# Versterkers.net
KiCad netlist of a schematic drawn in Altium Designer
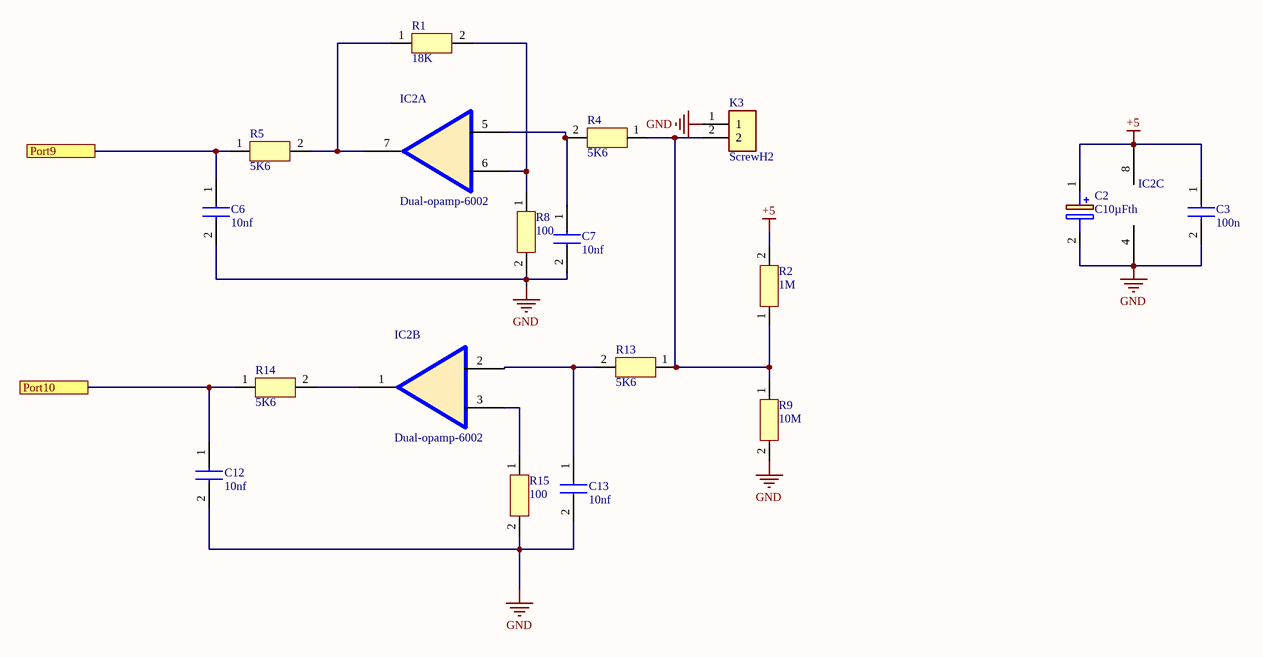
[diagram p0: Versterkers.SchDoc]

(export (version "E")
  (design (tool "Eeschema 10.0.6"))
  (components
    (comp (ref "C2")
      (value "C10µFth")
      (footprint "C10µFth")
      (description "Capacitor Polarised")
      (fields
        (field (name "MOUSER2 PART NUMBER") "667-ECA-1HM100I")
        (field (name "MANUFACTURER_PART_NUMBER") "ECA-1HM100I")
      )
      (libsource (lib "Soldeerbout_12002498") (part "C10µFth"))
    )
    (comp (ref "C3")
      (value "100n")
      (footprint "0805")
      (description "Capacitor")
      (fields (field (name "MANUFACTURER_PART_NUMBER") "C0805C301G5GACTU"))
      (libsource (lib "Soldeerbout_12002498") (part "C0805smd"))
    )
    (comp (ref "C6")
      (value "10nf")
      (footprint "0805")
      (description "Capacitor")
      (fields (field (name "MANUFACTURER_PART_NUMBER") "C0805C301G5GACTU"))
      (libsource (lib "Soldeerbout_12002498") (part "C0805smd"))
    )
    (comp (ref "C7")
      (value "10nf")
      (footprint "0805")
      (description "Capacitor")
      (fields (field (name "MANUFACTURER_PART_NUMBER") "C0805C301G5GACTU"))
      (libsource (lib "Soldeerbout_12002498") (part "C0805smd"))
    )
    (comp (ref "C12")
      (value "10nf")
      (footprint "0805")
      (description "Capacitor")
      (fields (field (name "MANUFACTURER_PART_NUMBER") "C0805C301G5GACTU"))
      (libsource (lib "Soldeerbout_12002498") (part "C0805smd"))
    )
    (comp (ref "C13")
      (value "10nf")
      (footprint "0805")
      (description "Capacitor")
      (fields (field (name "MANUFACTURER_PART_NUMBER") "C0805C301G5GACTU"))
      (libsource (lib "Soldeerbout_12002498") (part "C0805smd"))
    )
    (comp (ref "IC2")
      (value "Dual-opamp-6002")
      (footprint "Dual-opamp-6002")
      (description "Integrated Circuit")
      (fields
        (field (name "MOUSER2 PART NUMBER") "579-MCP6002-E/P")
        (field (name "MANUFACTURER_PART_NUMBER") "MCP6002-E/P")
      )
      (libsource (lib "Soldeerbout_12002498") (part "Dual-opamp-6002"))
    )
    (comp (ref "K3")
      (value "ScrewH2")
      (footprint "Soldeerbout_12002498:ScewH2")
      (description "Connector")
      (fields
        (field (name "MOUSER2 PART NUMBER") "490-TB007-508-02BE")
        (field (name "MANUFACTURER_PART_NUMBER") "TB007-508-02BE")
      )
      (libsource (lib "Soldeerbout_12002498") (part "ScrewH2"))
    )
    (comp (ref "R1")
      (value "18K")
      (footprint "0805")
      (description "Resistor")
      (fields (field (name "MANUFACTURER_PART_NUMBER") "TNPU0805500RAZEN00"))
      (libsource (lib "Soldeerbout_12002498") (part "R-0805"))
    )
    (comp (ref "R2")
      (value "1M")
      (footprint "0805")
      (description "Resistor")
      (fields (field (name "MANUFACTURER_PART_NUMBER") "TNPU0805500RAZEN00"))
      (libsource (lib "") (part "R-0805_2"))
    )
    (comp (ref "R4")
      (value "5K6")
      (footprint "0805")
      (description "Resistor")
      (fields (field (name "MANUFACTURER_PART_NUMBER") "TNPU0805500RAZEN00"))
      (libsource (lib "") (part "R-0805_3"))
    )
    (comp (ref "R5")
      (value "5K6")
      (footprint "0805")
      (description "Resistor")
      (fields (field (name "MANUFACTURER_PART_NUMBER") "TNPU0805500RAZEN00"))
      (libsource (lib "Soldeerbout_12002498") (part "R-0805"))
    )
    (comp (ref "R8")
      (value "100")
      (footprint "0805")
      (description "Resistor")
      (fields (field (name "MANUFACTURER_PART_NUMBER") "TNPU0805500RAZEN00"))
      (libsource (lib "") (part "R-0805_1"))
    )
    (comp (ref "R9")
      (value "10M")
      (footprint "0805")
      (description "Resistor")
      (fields (field (name "MANUFACTURER_PART_NUMBER") "TNPU0805500RAZEN00"))
      (libsource (lib "") (part "R-0805_1"))
    )
    (comp (ref "R13")
      (value "5K6")
      (footprint "0805")
      (description "Resistor")
      (fields (field (name "MANUFACTURER_PART_NUMBER") "TNPU0805500RAZEN00"))
      (libsource (lib "") (part "R-0805_3"))
    )
    (comp (ref "R14")
      (value "5K6")
      (footprint "0805")
      (description "Resistor")
      (fields (field (name "MANUFACTURER_PART_NUMBER") "TNPU0805500RAZEN00"))
      (libsource (lib "Soldeerbout_12002498") (part "R-0805"))
    )
    (comp (ref "R15")
      (value "100")
      (footprint "0805")
      (description "Resistor")
      (fields (field (name "MANUFACTURER_PART_NUMBER") "TNPU0805500RAZEN00"))
      (libsource (lib "") (part "R-0805_1"))
    )
  )
  (nets
    (net (code "1") (name "+5") (class "Default")
      (node (ref "C2") (pin "1") (pinfunction "+_1") (pintype "passive"))
      (node (ref "C3") (pin "1") (pinfunction "1_1") (pintype "passive"))
      (node (ref "IC2") (pin "8") (pinfunction "8_8") (pintype "passive"))
      (node (ref "R2") (pin "2") (pinfunction "2_2") (pintype "passive"))
    )
    (net (code "2") (name "/Port9") (class "Default")
      (node (ref "C6") (pin "1") (pinfunction "1_1") (pintype "passive"))
      (node (ref "R5") (pin "1") (pinfunction "1_1") (pintype "passive"))
    )
    (net (code "3") (name "/Port10") (class "Default")
      (node (ref "C12") (pin "1") (pinfunction "1_1") (pintype "passive"))
      (node (ref "R14") (pin "1") (pinfunction "1_1") (pintype "passive"))
    )
    (net (code "4") (name "GND") (class "Default")
      (node (ref "C12") (pin "2") (pinfunction "2_2") (pintype "passive"))
      (node (ref "C13") (pin "2") (pinfunction "2_2") (pintype "passive"))
      (node (ref "C2") (pin "2") (pinfunction "-_2") (pintype "passive"))
      (node (ref "C3") (pin "2") (pinfunction "2_2") (pintype "passive"))
      (node (ref "C6") (pin "2") (pinfunction "2_2") (pintype "passive"))
      (node (ref "C7") (pin "2") (pinfunction "2_2") (pintype "passive"))
      (node (ref "IC2") (pin "4") (pinfunction "9_4") (pintype "passive"))
      (node (ref "K3") (pin "1") (pinfunction "1_1") (pintype "passive"))
      (node (ref "R15") (pin "2") (pinfunction "2_2") (pintype "passive"))
      (node (ref "R8") (pin "2") (pinfunction "2_2") (pintype "passive"))
      (node (ref "R9") (pin "2") (pinfunction "2_2") (pintype "passive"))
    )
    (net (code "5") (name "Net-(IC2A-Vin)") (class "Default")
      (node (ref "C7") (pin "1") (pinfunction "1_1") (pintype "passive"))
      (node (ref "IC2") (pin "5") (pinfunction "Vin_5") (pintype "passive"))
      (node (ref "R4") (pin "2") (pinfunction "2_2") (pintype "passive"))
    )
    (net (code "6") (name "Net-(IC2A-Vin-)") (class "Default")
      (node (ref "IC2") (pin "6") (pinfunction "Vin-_6") (pintype "passive"))
      (node (ref "R1") (pin "2") (pinfunction "2_2") (pintype "passive"))
      (node (ref "R8") (pin "1") (pinfunction "1_1") (pintype "passive"))
    )
    (net (code "7") (name "Net-(IC2A-Vout)") (class "Default")
      (node (ref "IC2") (pin "7") (pinfunction "Vout_7") (pintype "passive"))
      (node (ref "R1") (pin "1") (pinfunction "1_1") (pintype "passive"))
      (node (ref "R5") (pin "2") (pinfunction "2_2") (pintype "passive"))
    )
    (net (code "8") (name "Net-(IC2B-Vin)") (class "Default")
      (node (ref "C13") (pin "1") (pinfunction "1_1") (pintype "passive"))
      (node (ref "IC2") (pin "2") (pinfunction "Vin_2") (pintype "passive"))
      (node (ref "R13") (pin "2") (pinfunction "2_2") (pintype "passive"))
    )
    (net (code "9") (name "Net-(IC2B-Vin-)") (class "Default")
      (node (ref "IC2") (pin "3") (pinfunction "Vin-_3") (pintype "passive"))
      (node (ref "R15") (pin "1") (pinfunction "1_1") (pintype "passive"))
    )
    (net (code "10") (name "Net-(IC2B-Vout)") (class "Default")
      (node (ref "IC2") (pin "1") (pinfunction "Vout_1") (pintype "passive"))
      (node (ref "R14") (pin "2") (pinfunction "2_2") (pintype "passive"))
    )
    (net (code "11") (name "Net-(K3-Pad2)") (class "Default")
      (node (ref "K3") (pin "2") (pinfunction "2_2") (pintype "passive"))
      (node (ref "R13") (pin "1") (pinfunction "1_1") (pintype "passive"))
      (node (ref "R2") (pin "1") (pinfunction "1_1") (pintype "passive"))
      (node (ref "R4") (pin "1") (pinfunction "1_1") (pintype "passive"))
      (node (ref "R9") (pin "1") (pinfunction "1_1") (pintype "passive"))
    )
  )
)
